# sft.net
KiCad netlist of a schematic drawn in Altium Designer
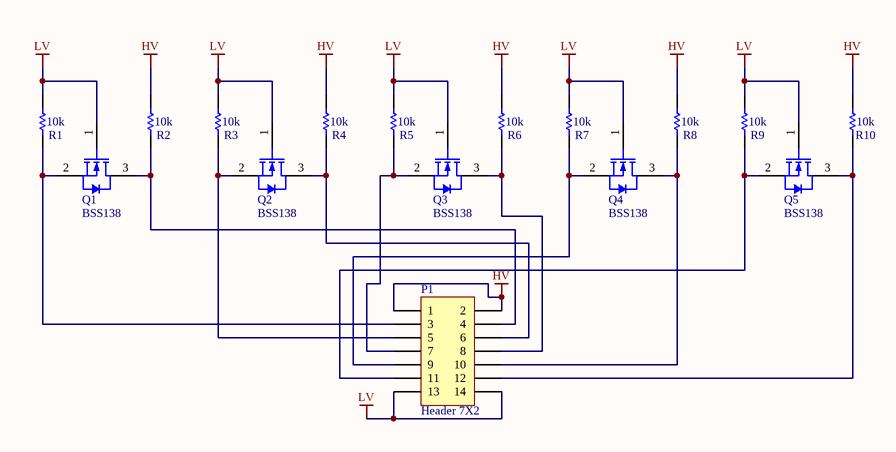
[diagram p0: sft.SchDoc]

(export (version "E")
  (design (tool "Eeschema 10.0.6"))
  (components
    (comp (ref "P1")
      (value "Header 7X2")
      (footprint "HDR2X7")
      (description "Header, 7-Pin, Dual row")
      (fields (field (name "PUBLISHER") "Altium Limited"))
      (libsource (lib "Miscellaneous Connectors") (part "Header 7X2"))
    )
    (comp (ref "Q1")
      (value "BSS138")
      (footprint "FAIR-SOT23-3_V")
      (fields (field (name "TOLERANCE") "30ppm"))
      (libsource (lib "symbol_library") (part "BSS138"))
    )
    (comp (ref "Q2")
      (value "BSS138")
      (footprint "FAIR-SOT23-3_V")
      (fields (field (name "TOLERANCE") "30ppm"))
      (libsource (lib "symbol_library") (part "BSS138"))
    )
    (comp (ref "Q3")
      (value "BSS138")
      (footprint "FAIR-SOT23-3_V")
      (fields (field (name "TOLERANCE") "30ppm"))
      (libsource (lib "symbol_library") (part "BSS138"))
    )
    (comp (ref "Q4")
      (value "BSS138")
      (footprint "FAIR-SOT23-3_V")
      (fields (field (name "TOLERANCE") "30ppm"))
      (libsource (lib "symbol_library") (part "BSS138"))
    )
    (comp (ref "Q5")
      (value "BSS138")
      (footprint "FAIR-SOT23-3_V")
      (fields (field (name "TOLERANCE") "30ppm"))
      (libsource (lib "symbol_library") (part "BSS138"))
    )
    (comp (ref "R1")
      (value "10k")
      (footprint "0603")
      (description "Generic 0603 Resistor")
      (libsource (lib "symbol_library") (part "R_0603"))
    )
    (comp (ref "R2")
      (value "10k")
      (footprint "0603")
      (description "Generic 0603 Resistor")
      (libsource (lib "symbol_library") (part "R_0603"))
    )
    (comp (ref "R3")
      (value "10k")
      (footprint "0603")
      (description "Generic 0603 Resistor")
      (libsource (lib "symbol_library") (part "R_0603"))
    )
    (comp (ref "R4")
      (value "10k")
      (footprint "0603")
      (description "Generic 0603 Resistor")
      (libsource (lib "symbol_library") (part "R_0603"))
    )
    (comp (ref "R5")
      (value "10k")
      (footprint "0603")
      (description "Generic 0603 Resistor")
      (libsource (lib "symbol_library") (part "R_0603"))
    )
    (comp (ref "R6")
      (value "10k")
      (footprint "0603")
      (description "Generic 0603 Resistor")
      (libsource (lib "symbol_library") (part "R_0603"))
    )
    (comp (ref "R7")
      (value "10k")
      (footprint "0603")
      (description "Generic 0603 Resistor")
      (libsource (lib "symbol_library") (part "R_0603"))
    )
    (comp (ref "R8")
      (value "10k")
      (footprint "0603")
      (description "Generic 0603 Resistor")
      (libsource (lib "symbol_library") (part "R_0603"))
    )
    (comp (ref "R9")
      (value "10k")
      (footprint "0603")
      (description "Generic 0603 Resistor")
      (libsource (lib "symbol_library") (part "R_0603"))
    )
    (comp (ref "R10")
      (value "10k")
      (footprint "0603")
      (description "Generic 0603 Resistor")
      (libsource (lib "symbol_library") (part "R_0603"))
    )
  )
  (nets
    (net (code "1") (name "HV") (class "Default")
      (node (ref "P1") (pin "1") (pinfunction "1_1") (pintype "passive"))
      (node (ref "P1") (pin "2") (pinfunction "2_2") (pintype "passive"))
      (node (ref "R10") (pin "2") (pinfunction "2_2") (pintype "passive"))
      (node (ref "R2") (pin "2") (pinfunction "2_2") (pintype "passive"))
      (node (ref "R4") (pin "2") (pinfunction "2_2") (pintype "passive"))
      (node (ref "R6") (pin "2") (pinfunction "2_2") (pintype "passive"))
      (node (ref "R8") (pin "2") (pinfunction "2_2") (pintype "passive"))
    )
    (net (code "2") (name "LV") (class "Default")
      (node (ref "P1") (pin "13") (pinfunction "13_13") (pintype "passive"))
      (node (ref "P1") (pin "14") (pinfunction "14_14") (pintype "passive"))
      (node (ref "Q1") (pin "1") (pinfunction "G_1") (pintype "passive"))
      (node (ref "Q2") (pin "1") (pinfunction "G_1") (pintype "passive"))
      (node (ref "Q3") (pin "1") (pinfunction "G_1") (pintype "passive"))
      (node (ref "Q4") (pin "1") (pinfunction "G_1") (pintype "passive"))
      (node (ref "Q5") (pin "1") (pinfunction "G_1") (pintype "passive"))
      (node (ref "R1") (pin "2") (pinfunction "2_2") (pintype "passive"))
      (node (ref "R3") (pin "2") (pinfunction "2_2") (pintype "passive"))
      (node (ref "R5") (pin "2") (pinfunction "2_2") (pintype "passive"))
      (node (ref "R7") (pin "2") (pinfunction "2_2") (pintype "passive"))
      (node (ref "R9") (pin "2") (pinfunction "2_2") (pintype "passive"))
    )
    (net (code "3") (name "Net-(Q1-D)") (class "Default")
      (node (ref "P1") (pin "4") (pinfunction "4_4") (pintype "passive"))
      (node (ref "Q1") (pin "3") (pinfunction "D_3") (pintype "passive"))
      (node (ref "R2") (pin "1") (pinfunction "1_1") (pintype "passive"))
    )
    (net (code "4") (name "Net-(Q1-S)") (class "Default")
      (node (ref "P1") (pin "3") (pinfunction "3_3") (pintype "passive"))
      (node (ref "Q1") (pin "2") (pinfunction "S_2") (pintype "passive"))
      (node (ref "R1") (pin "1") (pinfunction "1_1") (pintype "passive"))
    )
    (net (code "5") (name "Net-(Q2-D)") (class "Default")
      (node (ref "P1") (pin "6") (pinfunction "6_6") (pintype "passive"))
      (node (ref "Q2") (pin "3") (pinfunction "D_3") (pintype "passive"))
      (node (ref "R4") (pin "1") (pinfunction "1_1") (pintype "passive"))
    )
    (net (code "6") (name "Net-(Q2-S)") (class "Default")
      (node (ref "P1") (pin "5") (pinfunction "5_5") (pintype "passive"))
      (node (ref "Q2") (pin "2") (pinfunction "S_2") (pintype "passive"))
      (node (ref "R3") (pin "1") (pinfunction "1_1") (pintype "passive"))
    )
    (net (code "7") (name "Net-(Q3-D)") (class "Default")
      (node (ref "P1") (pin "8") (pinfunction "8_8") (pintype "passive"))
      (node (ref "Q3") (pin "3") (pinfunction "D_3") (pintype "passive"))
      (node (ref "R6") (pin "1") (pinfunction "1_1") (pintype "passive"))
    )
    (net (code "8") (name "Net-(Q3-S)") (class "Default")
      (node (ref "P1") (pin "7") (pinfunction "7_7") (pintype "passive"))
      (node (ref "Q3") (pin "2") (pinfunction "S_2") (pintype "passive"))
      (node (ref "R5") (pin "1") (pinfunction "1_1") (pintype "passive"))
    )
    (net (code "9") (name "Net-(Q4-D)") (class "Default")
      (node (ref "P1") (pin "10") (pinfunction "10_10") (pintype "passive"))
      (node (ref "Q4") (pin "3") (pinfunction "D_3") (pintype "passive"))
      (node (ref "R8") (pin "1") (pinfunction "1_1") (pintype "passive"))
    )
    (net (code "10") (name "Net-(Q4-S)") (class "Default")
      (node (ref "P1") (pin "9") (pinfunction "9_9") (pintype "passive"))
      (node (ref "Q4") (pin "2") (pinfunction "S_2") (pintype "passive"))
      (node (ref "R7") (pin "1") (pinfunction "1_1") (pintype "passive"))
    )
    (net (code "11") (name "Net-(Q5-D)") (class "Default")
      (node (ref "P1") (pin "12") (pinfunction "12_12") (pintype "passive"))
      (node (ref "Q5") (pin "3") (pinfunction "D_3") (pintype "passive"))
      (node (ref "R10") (pin "1") (pinfunction "1_1") (pintype "passive"))
    )
    (net (code "12") (name "Net-(Q5-S)") (class "Default")
      (node (ref "P1") (pin "11") (pinfunction "11_11") (pintype "passive"))
      (node (ref "Q5") (pin "2") (pinfunction "S_2") (pintype "passive"))
      (node (ref "R9") (pin "1") (pinfunction "1_1") (pintype "passive"))
    )
  )
)
